# three-phase_inverter.net
KiCad netlist of a schematic drawn in Altium Designer
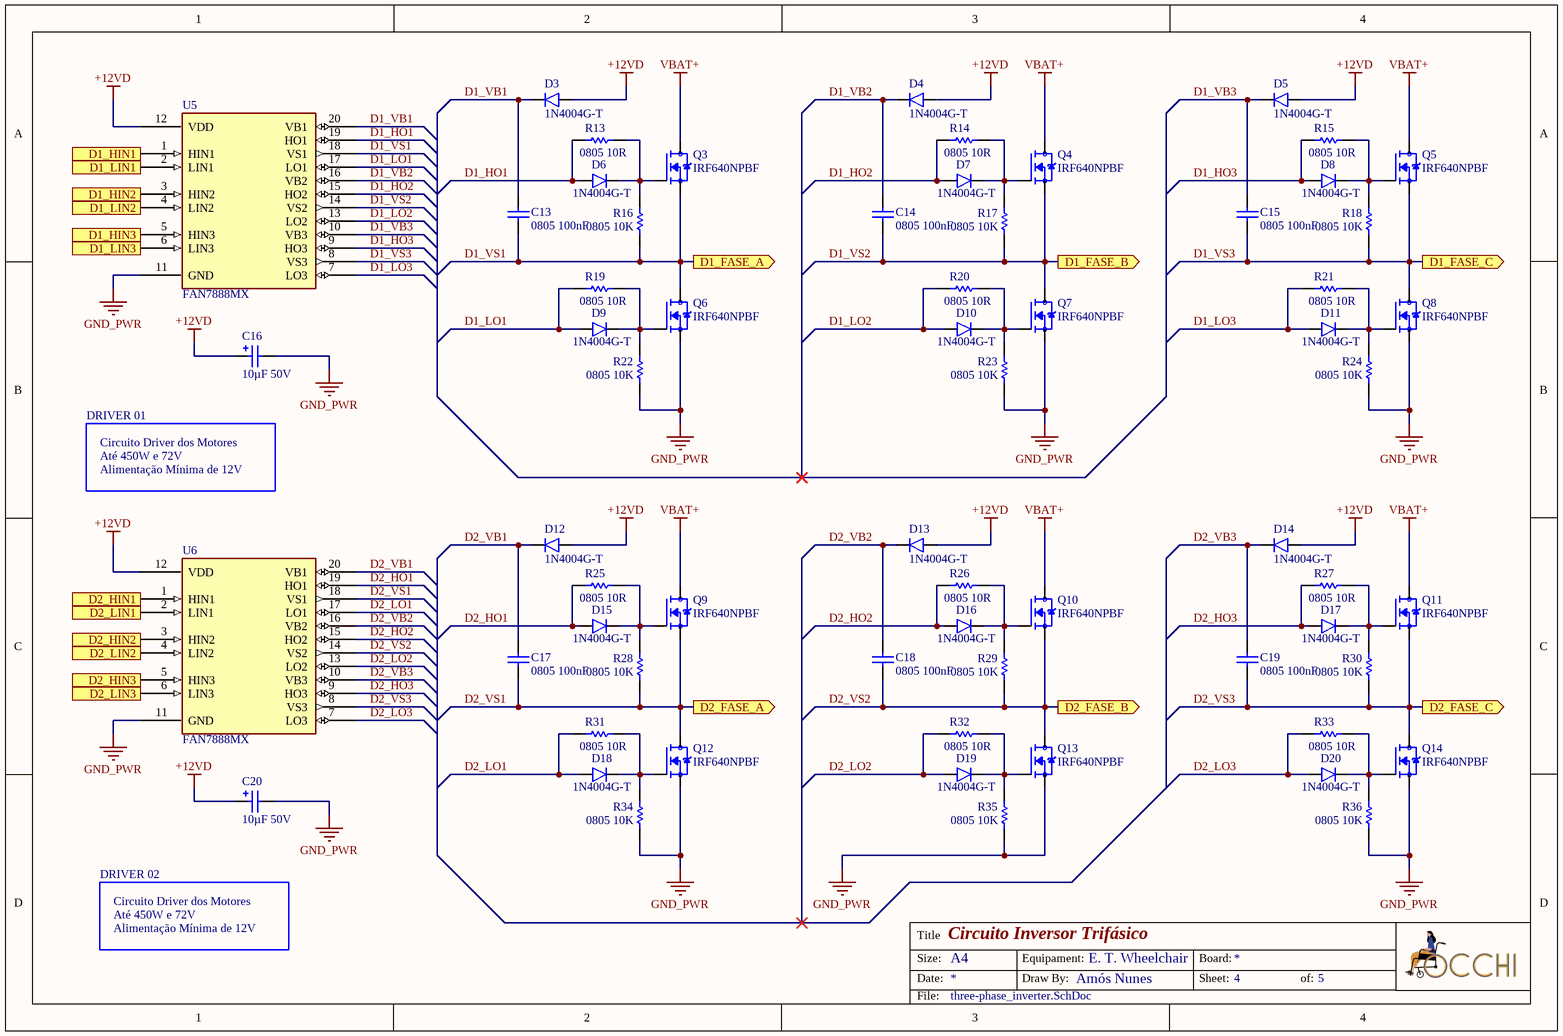
[diagram p0: three-phase_inverter.SchDoc]

(export (version "E")
  (design (tool "Eeschema 10.0.6"))
  (components
    (comp (ref "C13")
      (value "0805 100nF")
      (footprint "CAP0805")
      (description "CC Series 0805 0.1 uF 50 V ±10 % Tolerance X7R SMT Multilayer Ceramic Capacitor")
      (fields
        (field (name "MANUFACTURER") "Yageo")
        (field (name "MANUFACTURER PART NUMBER") "CC0805KRX7R9BB104")
      )
      (libsource (lib "occhi") (part "CC0805KRX7R9BB104"))
    )
    (comp (ref "C14")
      (value "0805 100nF")
      (footprint "CAP0805")
      (description "CC Series 0805 0.1 uF 50 V ±10 % Tolerance X7R SMT Multilayer Ceramic Capacitor")
      (fields
        (field (name "MANUFACTURER") "Yageo")
        (field (name "MANUFACTURER PART NUMBER") "CC0805KRX7R9BB104")
      )
      (libsource (lib "occhi") (part "CC0805KRX7R9BB104"))
    )
    (comp (ref "C15")
      (value "0805 100nF")
      (footprint "CAP0805")
      (description "CC Series 0805 0.1 uF 50 V ±10 % Tolerance X7R SMT Multilayer Ceramic Capacitor")
      (fields
        (field (name "MANUFACTURER") "Yageo")
        (field (name "MANUFACTURER PART NUMBER") "CC0805KRX7R9BB104")
      )
      (libsource (lib "occhi") (part "CC0805KRX7R9BB104"))
    )
    (comp (ref "C16")
      (value "10µF 50V")
      (footprint "CAP_PK/PZ_6P3X11_LOW_RUB")
      (description "10uF ±20% 50V 5000hrs@105°C AEC_D5x11mm_2mm_TM")
      (fields
        (field (name "MANUFACTURER_PART_NUMBER") "16PK330MEFC6.3X11")
        (field (name "MANUFACTURER") "Rubycon")
        (field (name "COPYRIGHT") "Copyright (C) 2021 Ultra Librarian. All rights reserved.")
      )
      (libsource (lib "occhi") (part "50YXF10MEFC5X11"))
    )
    (comp (ref "C17")
      (value "0805 100nF")
      (footprint "CAP0805")
      (description "CC Series 0805 0.1 uF 50 V ±10 % Tolerance X7R SMT Multilayer Ceramic Capacitor")
      (fields
        (field (name "MANUFACTURER") "Yageo")
        (field (name "MANUFACTURER PART NUMBER") "CC0805KRX7R9BB104")
      )
      (libsource (lib "occhi") (part "CC0805KRX7R9BB104"))
    )
    (comp (ref "C18")
      (value "0805 100nF")
      (footprint "CAP0805")
      (description "CC Series 0805 0.1 uF 50 V ±10 % Tolerance X7R SMT Multilayer Ceramic Capacitor")
      (fields
        (field (name "MANUFACTURER") "Yageo")
        (field (name "MANUFACTURER PART NUMBER") "CC0805KRX7R9BB104")
      )
      (libsource (lib "occhi") (part "CC0805KRX7R9BB104"))
    )
    (comp (ref "C19")
      (value "0805 100nF")
      (footprint "CAP0805")
      (description "CC Series 0805 0.1 uF 50 V ±10 % Tolerance X7R SMT Multilayer Ceramic Capacitor")
      (fields
        (field (name "MANUFACTURER") "Yageo")
        (field (name "MANUFACTURER PART NUMBER") "CC0805KRX7R9BB104")
      )
      (libsource (lib "occhi") (part "CC0805KRX7R9BB104"))
    )
    (comp (ref "C20")
      (value "10µF 50V")
      (footprint "CAP_PK/PZ_6P3X11_LOW_RUB")
      (description "10uF ±20% 50V 5000hrs@105°C AEC_D5x11mm_2mm_TM")
      (fields
        (field (name "MANUFACTURER_PART_NUMBER") "16PK330MEFC6.3X11")
        (field (name "MANUFACTURER") "Rubycon")
        (field (name "COPYRIGHT") "Copyright (C) 2021 Ultra Librarian. All rights reserved.")
      )
      (libsource (lib "occhi") (part "50YXF10MEFC5X11"))
    )
    (comp (ref "D3")
      (value "1N4004G-T")
      (footprint "DO41-10")
      (description "Diode Standard Recovery Rectifier 400V 1A 2-Pin DO-41 T/R")
      (fields (field (name "MANUFACTURER") "Diodes"))
      (libsource (lib "occhi") (part "1N4004G-T"))
    )
    (comp (ref "D4")
      (value "1N4004G-T")
      (footprint "DO41-10")
      (description "Diode Standard Recovery Rectifier 400V 1A 2-Pin DO-41 T/R")
      (fields (field (name "MANUFACTURER") "Diodes"))
      (libsource (lib "occhi") (part "1N4004G-T"))
    )
    (comp (ref "D5")
      (value "1N4004G-T")
      (footprint "DO41-10")
      (description "Diode Standard Recovery Rectifier 400V 1A 2-Pin DO-41 T/R")
      (fields (field (name "MANUFACTURER") "Diodes"))
      (libsource (lib "occhi") (part "1N4004G-T"))
    )
    (comp (ref "D6")
      (value "1N4004G-T")
      (footprint "DO41-10")
      (description "Diode Standard Recovery Rectifier 400V 1A 2-Pin DO-41 T/R")
      (fields (field (name "MANUFACTURER") "Diodes"))
      (libsource (lib "occhi") (part "1N4004G-T"))
    )
    (comp (ref "D7")
      (value "1N4004G-T")
      (footprint "DO41-10")
      (description "Diode Standard Recovery Rectifier 400V 1A 2-Pin DO-41 T/R")
      (fields (field (name "MANUFACTURER") "Diodes"))
      (libsource (lib "occhi") (part "1N4004G-T"))
    )
    (comp (ref "D8")
      (value "1N4004G-T")
      (footprint "DO41-10")
      (description "Diode Standard Recovery Rectifier 400V 1A 2-Pin DO-41 T/R")
      (fields (field (name "MANUFACTURER") "Diodes"))
      (libsource (lib "occhi") (part "1N4004G-T"))
    )
    (comp (ref "D9")
      (value "1N4004G-T")
      (footprint "DO41-10")
      (description "Diode Standard Recovery Rectifier 400V 1A 2-Pin DO-41 T/R")
      (fields (field (name "MANUFACTURER") "Diodes"))
      (libsource (lib "occhi") (part "1N4004G-T"))
    )
    (comp (ref "D10")
      (value "1N4004G-T")
      (footprint "DO41-10")
      (description "Diode Standard Recovery Rectifier 400V 1A 2-Pin DO-41 T/R")
      (fields (field (name "MANUFACTURER") "Diodes"))
      (libsource (lib "occhi") (part "1N4004G-T"))
    )
    (comp (ref "D11")
      (value "1N4004G-T")
      (footprint "DO41-10")
      (description "Diode Standard Recovery Rectifier 400V 1A 2-Pin DO-41 T/R")
      (fields (field (name "MANUFACTURER") "Diodes"))
      (libsource (lib "occhi") (part "1N4004G-T"))
    )
    (comp (ref "D12")
      (value "1N4004G-T")
      (footprint "DO41-10")
      (description "Diode Standard Recovery Rectifier 400V 1A 2-Pin DO-41 T/R")
      (fields (field (name "MANUFACTURER") "Diodes"))
      (libsource (lib "occhi") (part "1N4004G-T"))
    )
    (comp (ref "D13")
      (value "1N4004G-T")
      (footprint "DO41-10")
      (description "Diode Standard Recovery Rectifier 400V 1A 2-Pin DO-41 T/R")
      (fields (field (name "MANUFACTURER") "Diodes"))
      (libsource (lib "occhi") (part "1N4004G-T"))
    )
    (comp (ref "D14")
      (value "1N4004G-T")
      (footprint "DO41-10")
      (description "Diode Standard Recovery Rectifier 400V 1A 2-Pin DO-41 T/R")
      (fields (field (name "MANUFACTURER") "Diodes"))
      (libsource (lib "occhi") (part "1N4004G-T"))
    )
    (comp (ref "D15")
      (value "1N4004G-T")
      (footprint "DO41-10")
      (description "Diode Standard Recovery Rectifier 400V 1A 2-Pin DO-41 T/R")
      (fields (field (name "MANUFACTURER") "Diodes"))
      (libsource (lib "occhi") (part "1N4004G-T"))
    )
    (comp (ref "D16")
      (value "1N4004G-T")
      (footprint "DO41-10")
      (description "Diode Standard Recovery Rectifier 400V 1A 2-Pin DO-41 T/R")
      (fields (field (name "MANUFACTURER") "Diodes"))
      (libsource (lib "occhi") (part "1N4004G-T"))
    )
    (comp (ref "D17")
      (value "1N4004G-T")
      (footprint "DO41-10")
      (description "Diode Standard Recovery Rectifier 400V 1A 2-Pin DO-41 T/R")
      (fields (field (name "MANUFACTURER") "Diodes"))
      (libsource (lib "occhi") (part "1N4004G-T"))
    )
    (comp (ref "D18")
      (value "1N4004G-T")
      (footprint "DO41-10")
      (description "Diode Standard Recovery Rectifier 400V 1A 2-Pin DO-41 T/R")
      (fields (field (name "MANUFACTURER") "Diodes"))
      (libsource (lib "occhi") (part "1N4004G-T"))
    )
    (comp (ref "D19")
      (value "1N4004G-T")
      (footprint "DO41-10")
      (description "Diode Standard Recovery Rectifier 400V 1A 2-Pin DO-41 T/R")
      (fields (field (name "MANUFACTURER") "Diodes"))
      (libsource (lib "occhi") (part "1N4004G-T"))
    )
    (comp (ref "D20")
      (value "1N4004G-T")
      (footprint "DO41-10")
      (description "Diode Standard Recovery Rectifier 400V 1A 2-Pin DO-41 T/R")
      (fields (field (name "MANUFACTURER") "Diodes"))
      (libsource (lib "occhi") (part "1N4004G-T"))
    )
    (comp (ref "Q3")
      (value "IRF640NPBF")
      (footprint "TO220AB_VIS")
      (description "Mosfet, Power; N-ch; Vdss 200V; Rds(on) 0.15 Ohm; Id 18A; TO-220AB; Pd 150W; Vgs +/-20V")
      (fields (field (name "MF") "Infineon") (field (name "MANUFACTURER") "International Rectifier"))
      (libsource (lib "occhi") (part "IRF640NPBF"))
    )
    (comp (ref "Q4")
      (value "IRF640NPBF")
      (footprint "TO220AB_VIS")
      (description "Mosfet, Power; N-ch; Vdss 200V; Rds(on) 0.15 Ohm; Id 18A; TO-220AB; Pd 150W; Vgs +/-20V")
      (fields (field (name "MF") "Infineon") (field (name "MANUFACTURER") "International Rectifier"))
      (libsource (lib "occhi") (part "IRF640NPBF"))
    )
    (comp (ref "Q5")
      (value "IRF640NPBF")
      (footprint "TO220AB_VIS")
      (description "Mosfet, Power; N-ch; Vdss 200V; Rds(on) 0.15 Ohm; Id 18A; TO-220AB; Pd 150W; Vgs +/-20V")
      (fields (field (name "MF") "Infineon") (field (name "MANUFACTURER") "International Rectifier"))
      (libsource (lib "occhi") (part "IRF640NPBF"))
    )
    (comp (ref "Q6")
      (value "IRF640NPBF")
      (footprint "TO220AB_VIS")
      (description "Mosfet, Power; N-ch; Vdss 200V; Rds(on) 0.15 Ohm; Id 18A; TO-220AB; Pd 150W; Vgs +/-20V")
      (fields (field (name "MF") "Infineon") (field (name "MANUFACTURER") "International Rectifier"))
      (libsource (lib "occhi") (part "IRF640NPBF"))
    )
    (comp (ref "Q7")
      (value "IRF640NPBF")
      (footprint "TO220AB_VIS")
      (description "Mosfet, Power; N-ch; Vdss 200V; Rds(on) 0.15 Ohm; Id 18A; TO-220AB; Pd 150W; Vgs +/-20V")
      (fields (field (name "MF") "Infineon") (field (name "MANUFACTURER") "International Rectifier"))
      (libsource (lib "occhi") (part "IRF640NPBF"))
    )
    (comp (ref "Q8")
      (value "IRF640NPBF")
      (footprint "TO220AB_VIS")
      (description "Mosfet, Power; N-ch; Vdss 200V; Rds(on) 0.15 Ohm; Id 18A; TO-220AB; Pd 150W; Vgs +/-20V")
      (fields (field (name "MF") "Infineon") (field (name "MANUFACTURER") "International Rectifier"))
      (libsource (lib "occhi") (part "IRF640NPBF"))
    )
    (comp (ref "Q9")
      (value "IRF640NPBF")
      (footprint "TO220AB_VIS")
      (description "Mosfet, Power; N-ch; Vdss 200V; Rds(on) 0.15 Ohm; Id 18A; TO-220AB; Pd 150W; Vgs +/-20V")
      (fields (field (name "MF") "Infineon") (field (name "MANUFACTURER") "International Rectifier"))
      (libsource (lib "occhi") (part "IRF640NPBF"))
    )
    (comp (ref "Q10")
      (value "IRF640NPBF")
      (footprint "TO220AB_VIS")
      (description "Mosfet, Power; N-ch; Vdss 200V; Rds(on) 0.15 Ohm; Id 18A; TO-220AB; Pd 150W; Vgs +/-20V")
      (fields (field (name "MF") "Infineon") (field (name "MANUFACTURER") "International Rectifier"))
      (libsource (lib "occhi") (part "IRF640NPBF"))
    )
    (comp (ref "Q11")
      (value "IRF640NPBF")
      (footprint "TO220AB_VIS")
      (description "Mosfet, Power; N-ch; Vdss 200V; Rds(on) 0.15 Ohm; Id 18A; TO-220AB; Pd 150W; Vgs +/-20V")
      (fields (field (name "MF") "Infineon") (field (name "MANUFACTURER") "International Rectifier"))
      (libsource (lib "occhi") (part "IRF640NPBF"))
    )
    (comp (ref "Q12")
      (value "IRF640NPBF")
      (footprint "TO220AB_VIS")
      (description "Mosfet, Power; N-ch; Vdss 200V; Rds(on) 0.15 Ohm; Id 18A; TO-220AB; Pd 150W; Vgs +/-20V")
      (fields (field (name "MF") "Infineon") (field (name "MANUFACTURER") "International Rectifier"))
      (libsource (lib "occhi") (part "IRF640NPBF"))
    )
    (comp (ref "Q13")
      (value "IRF640NPBF")
      (footprint "TO220AB_VIS")
      (description "Mosfet, Power; N-ch; Vdss 200V; Rds(on) 0.15 Ohm; Id 18A; TO-220AB; Pd 150W; Vgs +/-20V")
      (fields (field (name "MF") "Infineon") (field (name "MANUFACTURER") "International Rectifier"))
      (libsource (lib "occhi") (part "IRF640NPBF"))
    )
    (comp (ref "Q14")
      (value "IRF640NPBF")
      (footprint "TO220AB_VIS")
      (description "Mosfet, Power; N-ch; Vdss 200V; Rds(on) 0.15 Ohm; Id 18A; TO-220AB; Pd 150W; Vgs +/-20V")
      (fields (field (name "MF") "Infineon") (field (name "MANUFACTURER") "International Rectifier"))
      (libsource (lib "occhi") (part "IRF640NPBF"))
    )
    (comp (ref "R13")
      (value "0805 10R")
      (footprint "CAP0805")
      (description "10R Ohms ± 1.00% 0.125W ± 200ppm/℃ 0805")
      (fields
        (field (name "MANUFACTURER") "Yageo")
        (field (name "MANUFACTURER PART NUMBER") "RC0805FR-0710RL")
      )
      (libsource (lib "occhi") (part "RC0805FR-0710RL"))
    )
    (comp (ref "R14")
      (value "0805 10R")
      (footprint "CAP0805")
      (description "10R Ohms ± 1.00% 0.125W ± 200ppm/℃ 0805")
      (fields
        (field (name "MANUFACTURER") "Yageo")
        (field (name "MANUFACTURER PART NUMBER") "RC0805FR-0710RL")
      )
      (libsource (lib "occhi") (part "RC0805FR-0710RL"))
    )
    (comp (ref "R15")
      (value "0805 10R")
      (footprint "CAP0805")
      (description "10R Ohms ± 1.00% 0.125W ± 200ppm/℃ 0805")
      (fields
        (field (name "MANUFACTURER") "Yageo")
        (field (name "MANUFACTURER PART NUMBER") "RC0805FR-0710RL")
      )
      (libsource (lib "occhi") (part "RC0805FR-0710RL"))
    )
    (comp (ref "R16")
      (value "0805 10K")
      (footprint "RES0805")
      (description "10K Omhs 0805 ± 1.00% 0.125W ± 100ppm/℃")
      (fields
        (field (name "MANUFACTURER") "Yageo")
        (field (name "MANUFACTURER PART NUMBER") "RC0603FR-0710KL")
      )
      (libsource (lib "occhi") (part "RC0805FR-0710KL"))
    )
    (comp (ref "R17")
      (value "0805 10K")
      (footprint "RES0805")
      (description "10K Omhs 0805 ± 1.00% 0.125W ± 100ppm/℃")
      (fields
        (field (name "MANUFACTURER") "Yageo")
        (field (name "MANUFACTURER PART NUMBER") "RC0603FR-0710KL")
      )
      (libsource (lib "occhi") (part "RC0805FR-0710KL"))
    )
    (comp (ref "R18")
      (value "0805 10K")
      (footprint "RES0805")
      (description "10K Omhs 0805 ± 1.00% 0.125W ± 100ppm/℃")
      (fields
        (field (name "MANUFACTURER") "Yageo")
        (field (name "MANUFACTURER PART NUMBER") "RC0603FR-0710KL")
      )
      (libsource (lib "occhi") (part "RC0805FR-0710KL"))
    )
    (comp (ref "R19")
      (value "0805 10R")
      (footprint "CAP0805")
      (description "10R Ohms ± 1.00% 0.125W ± 200ppm/℃ 0805")
      (fields
        (field (name "MANUFACTURER") "Yageo")
        (field (name "MANUFACTURER PART NUMBER") "RC0805FR-0710RL")
      )
      (libsource (lib "occhi") (part "RC0805FR-0710RL"))
    )
    (comp (ref "R20")
      (value "0805 10R")
      (footprint "CAP0805")
      (description "10R Ohms ± 1.00% 0.125W ± 200ppm/℃ 0805")
      (fields
        (field (name "MANUFACTURER") "Yageo")
        (field (name "MANUFACTURER PART NUMBER") "RC0805FR-0710RL")
      )
      (libsource (lib "occhi") (part "RC0805FR-0710RL"))
    )
    (comp (ref "R21")
      (value "0805 10R")
      (footprint "CAP0805")
      (description "10R Ohms ± 1.00% 0.125W ± 200ppm/℃ 0805")
      (fields
        (field (name "MANUFACTURER") "Yageo")
        (field (name "MANUFACTURER PART NUMBER") "RC0805FR-0710RL")
      )
      (libsource (lib "occhi") (part "RC0805FR-0710RL"))
    )
    (comp (ref "R22")
      (value "0805 10K")
      (footprint "RES0805")
      (description "10K Omhs 0805 ± 1.00% 0.125W ± 100ppm/℃")
      (fields
        (field (name "MANUFACTURER") "Yageo")
        (field (name "MANUFACTURER PART NUMBER") "RC0603FR-0710KL")
      )
      (libsource (lib "occhi") (part "RC0805FR-0710KL"))
    )
    (comp (ref "R23")
      (value "0805 10K")
      (footprint "RES0805")
      (description "10K Omhs 0805 ± 1.00% 0.125W ± 100ppm/℃")
      (fields
        (field (name "MANUFACTURER") "Yageo")
        (field (name "MANUFACTURER PART NUMBER") "RC0603FR-0710KL")
      )
      (libsource (lib "occhi") (part "RC0805FR-0710KL"))
    )
    (comp (ref "R24")
      (value "0805 10K")
      (footprint "RES0805")
      (description "10K Omhs 0805 ± 1.00% 0.125W ± 100ppm/℃")
      (fields
        (field (name "MANUFACTURER") "Yageo")
        (field (name "MANUFACTURER PART NUMBER") "RC0603FR-0710KL")
      )
      (libsource (lib "occhi") (part "RC0805FR-0710KL"))
    )
    (comp (ref "R25")
      (value "0805 10R")
      (footprint "CAP0805")
      (description "10R Ohms ± 1.00% 0.125W ± 200ppm/℃ 0805")
      (fields
        (field (name "MANUFACTURER") "Yageo")
        (field (name "MANUFACTURER PART NUMBER") "RC0805FR-0710RL")
      )
      (libsource (lib "occhi") (part "RC0805FR-0710RL"))
    )
    (comp (ref "R26")
      (value "0805 10R")
      (footprint "CAP0805")
      (description "10R Ohms ± 1.00% 0.125W ± 200ppm/℃ 0805")
      (fields
        (field (name "MANUFACTURER") "Yageo")
        (field (name "MANUFACTURER PART NUMBER") "RC0805FR-0710RL")
      )
      (libsource (lib "occhi") (part "RC0805FR-0710RL"))
    )
    (comp (ref "R27")
      (value "0805 10R")
      (footprint "CAP0805")
      (description "10R Ohms ± 1.00% 0.125W ± 200ppm/℃ 0805")
      (fields
        (field (name "MANUFACTURER") "Yageo")
        (field (name "MANUFACTURER PART NUMBER") "RC0805FR-0710RL")
      )
      (libsource (lib "occhi") (part "RC0805FR-0710RL"))
    )
    (comp (ref "R28")
      (value "0805 10K")
      (footprint "RES0805")
      (description "10K Omhs 0805 ± 1.00% 0.125W ± 100ppm/℃")
      (fields
        (field (name "MANUFACTURER") "Yageo")
        (field (name "MANUFACTURER PART NUMBER") "RC0603FR-0710KL")
      )
      (libsource (lib "occhi") (part "RC0805FR-0710KL"))
    )
    (comp (ref "R29")
      (value "0805 10K")
      (footprint "RES0805")
      (description "10K Omhs 0805 ± 1.00% 0.125W ± 100ppm/℃")
      (fields
        (field (name "MANUFACTURER") "Yageo")
        (field (name "MANUFACTURER PART NUMBER") "RC0603FR-0710KL")
      )
      (libsource (lib "occhi") (part "RC0805FR-0710KL"))
    )
    (comp (ref "R30")
      (value "0805 10K")
      (footprint "RES0805")
      (description "10K Omhs 0805 ± 1.00% 0.125W ± 100ppm/℃")
      (fields
        (field (name "MANUFACTURER") "Yageo")
        (field (name "MANUFACTURER PART NUMBER") "RC0603FR-0710KL")
      )
      (libsource (lib "occhi") (part "RC0805FR-0710KL"))
    )
    (comp (ref "R31")
      (value "0805 10R")
      (footprint "CAP0805")
      (description "10R Ohms ± 1.00% 0.125W ± 200ppm/℃ 0805")
      (fields
        (field (name "MANUFACTURER") "Yageo")
        (field (name "MANUFACTURER PART NUMBER") "RC0805FR-0710RL")
      )
      (libsource (lib "occhi") (part "RC0805FR-0710RL"))
    )
    (comp (ref "R32")
      (value "0805 10R")
      (footprint "CAP0805")
      (description "10R Ohms ± 1.00% 0.125W ± 200ppm/℃ 0805")
      (fields
        (field (name "MANUFACTURER") "Yageo")
        (field (name "MANUFACTURER PART NUMBER") "RC0805FR-0710RL")
      )
      (libsource (lib "occhi") (part "RC0805FR-0710RL"))
    )
    (comp (ref "R33")
      (value "0805 10R")
      (footprint "CAP0805")
      (description "10R Ohms ± 1.00% 0.125W ± 200ppm/℃ 0805")
      (fields
        (field (name "MANUFACTURER") "Yageo")
        (field (name "MANUFACTURER PART NUMBER") "RC0805FR-0710RL")
      )
      (libsource (lib "occhi") (part "RC0805FR-0710RL"))
    )
    (comp (ref "R34")
      (value "0805 10K")
      (footprint "RES0805")
      (description "10K Omhs 0805 ± 1.00% 0.125W ± 100ppm/℃")
      (fields
        (field (name "MANUFACTURER") "Yageo")
        (field (name "MANUFACTURER PART NUMBER") "RC0603FR-0710KL")
      )
      (libsource (lib "occhi") (part "RC0805FR-0710KL"))
    )
    (comp (ref "R35")
      (value "0805 10K")
      (footprint "RES0805")
      (description "10K Omhs 0805 ± 1.00% 0.125W ± 100ppm/℃")
      (fields
        (field (name "MANUFACTURER") "Yageo")
        (field (name "MANUFACTURER PART NUMBER") "RC0603FR-0710KL")
      )
      (libsource (lib "occhi") (part "RC0805FR-0710KL"))
    )
    (comp (ref "R36")
      (value "0805 10K")
      (footprint "RES0805")
      (description "10K Omhs 0805 ± 1.00% 0.125W ± 100ppm/℃")
      (fields
        (field (name "MANUFACTURER") "Yageo")
        (field (name "MANUFACTURER PART NUMBER") "RC0603FR-0710KL")
      )
      (libsource (lib "occhi") (part "RC0805FR-0710KL"))
    )
    (comp (ref "U5")
      (value "FAN7888MX")
      (footprint "SOIC20_13X7P6_ONS")
      (description "Driver 200V 0.65A 6-OUT Hi/Lo Side Half Brdg Non-Inv 20-Pin SOIC W T/R")
      (fields
        (field (name "MANUFACTURER") "ON Semiconductor / Fairchild")
        (field (name "COPYRIGHT") "Copyright (C) 2022 Ultra Librarian. All rights reserved.")
      )
      (libsource (lib "occhi") (part "FAN7888MX"))
    )
    (comp (ref "U6")
      (value "FAN7888MX")
      (footprint "SOIC20_13X7P6_ONS")
      (description "Driver 200V 0.65A 6-OUT Hi/Lo Side Half Brdg Non-Inv 20-Pin SOIC W T/R")
      (fields
        (field (name "MANUFACTURER") "ON Semiconductor / Fairchild")
        (field (name "COPYRIGHT") "Copyright (C) 2022 Ultra Librarian. All rights reserved.")
      )
      (libsource (lib "occhi") (part "FAN7888MX"))
    )
  )
  (nets
    (net (code "1") (name "+12VD") (class "Default")
      (node (ref "C16") (pin "1") (pinfunction "1_1") (pintype "passive"))
      (node (ref "C20") (pin "1") (pinfunction "1_1") (pintype "passive"))
      (node (ref "D12") (pin "2") (pinfunction "A_2") (pintype "passive"))
      (node (ref "D13") (pin "2") (pinfunction "A_2") (pintype "passive"))
      (node (ref "D14") (pin "2") (pinfunction "A_2") (pintype "passive"))
      (node (ref "D3") (pin "2") (pinfunction "A_2") (pintype "passive"))
      (node (ref "D4") (pin "2") (pinfunction "A_2") (pintype "passive"))
      (node (ref "D5") (pin "2") (pinfunction "A_2") (pintype "passive"))
      (node (ref "U5") (pin "12") (pinfunction "VDD_12") (pintype "power_in"))
      (node (ref "U6") (pin "12") (pinfunction "VDD_12") (pintype "power_in"))
    )
    (net (code "2") (name "/D1_HIN1") (class "Default")
      (node (ref "U5") (pin "1") (pinfunction "HIN1_1") (pintype "input"))
    )
    (net (code "3") (name "/D1_HIN2") (class "Default")
      (node (ref "U5") (pin "3") (pinfunction "HIN2_3") (pintype "input"))
    )
    (net (code "4") (name "/D1_HIN3") (class "Default")
      (node (ref "U5") (pin "5") (pinfunction "HIN3_5") (pintype "input"))
    )
    (net (code "5") (name "/D1_HO1") (class "Default")
      (node (ref "D6") (pin "2") (pinfunction "A_2") (pintype "passive"))
      (node (ref "R13") (pin "1") (pinfunction "1_1") (pintype "passive"))
      (node (ref "U5") (pin "19") (pinfunction "HO1_19") (pintype "bidirectional"))
    )
    (net (code "6") (name "/D1_HO2") (class "Default")
      (node (ref "D7") (pin "2") (pinfunction "A_2") (pintype "passive"))
      (node (ref "R14") (pin "1") (pinfunction "1_1") (pintype "passive"))
      (node (ref "U5") (pin "15") (pinfunction "HO2_15") (pintype "bidirectional"))
    )
    (net (code "7") (name "/D1_HO3") (class "Default")
      (node (ref "D8") (pin "2") (pinfunction "A_2") (pintype "passive"))
      (node (ref "R15") (pin "1") (pinfunction "1_1") (pintype "passive"))
      (node (ref "U5") (pin "9") (pinfunction "HO3_9") (pintype "bidirectional"))
    )
    (net (code "8") (name "/D1_LIN1") (class "Default")
      (node (ref "U5") (pin "2") (pinfunction "LIN1_2") (pintype "input"))
    )
    (net (code "9") (name "/D1_LIN2") (class "Default")
      (node (ref "U5") (pin "4") (pinfunction "LIN2_4") (pintype "input"))
    )
    (net (code "10") (name "/D1_LIN3") (class "Default")
      (node (ref "U5") (pin "6") (pinfunction "LIN3_6") (pintype "input"))
    )
    (net (code "11") (name "/D1_LO1") (class "Default")
      (node (ref "D9") (pin "2") (pinfunction "A_2") (pintype "passive"))
      (node (ref "R19") (pin "1") (pinfunction "1_1") (pintype "passive"))
      (node (ref "U5") (pin "17") (pinfunction "LO1_17") (pintype "bidirectional"))
    )
    (net (code "12") (name "/D1_LO2") (class "Default")
      (node (ref "D10") (pin "2") (pinfunction "A_2") (pintype "passive"))
      (node (ref "R20") (pin "1") (pinfunction "1_1") (pintype "passive"))
      (node (ref "U5") (pin "13") (pinfunction "LO2_13") (pintype "bidirectional"))
    )
    (net (code "13") (name "/D1_LO3") (class "Default")
      (node (ref "D11") (pin "2") (pinfunction "A_2") (pintype "passive"))
      (node (ref "R21") (pin "1") (pinfunction "1_1") (pintype "passive"))
      (node (ref "U5") (pin "7") (pinfunction "LO3_7") (pintype "bidirectional"))
    )
    (net (code "14") (name "/D1_VB1") (class "Default")
      (node (ref "C13") (pin "1") (pinfunction "1_1") (pintype "passive"))
      (node (ref "D3") (pin "1") (pinfunction "K_1") (pintype "passive"))
      (node (ref "U5") (pin "20") (pinfunction "VB1_20") (pintype "bidirectional"))
    )
    (net (code "15") (name "/D1_VB2") (class "Default")
      (node (ref "C14") (pin "1") (pinfunction "1_1") (pintype "passive"))
      (node (ref "D4") (pin "1") (pinfunction "K_1") (pintype "passive"))
      (node (ref "U5") (pin "16") (pinfunction "VB2_16") (pintype "bidirectional"))
    )
    (net (code "16") (name "/D1_VB3") (class "Default")
      (node (ref "C15") (pin "1") (pinfunction "1_1") (pintype "passive"))
      (node (ref "D5") (pin "1") (pinfunction "K_1") (pintype "passive"))
      (node (ref "U5") (pin "10") (pinfunction "VB3_10") (pintype "bidirectional"))
    )
    (net (code "17") (name "/D1_VS1") (class "Default")
      (node (ref "C13") (pin "2") (pinfunction "2_2") (pintype "passive"))
      (node (ref "Q3") (pin "3") (pinfunction "S_3") (pintype "passive"))
      (node (ref "Q6") (pin "2") (pinfunction "D_2") (pintype "passive"))
      (node (ref "R16") (pin "2") (pinfunction "2_2") (pintype "passive"))
      (node (ref "U5") (pin "18") (pinfunction "VS1_18") (pintype "output"))
    )
    (net (code "18") (name "/D1_VS2") (class "Default")
      (node (ref "C14") (pin "2") (pinfunction "2_2") (pintype "passive"))
      (node (ref "Q4") (pin "3") (pinfunction "S_3") (pintype "passive"))
      (node (ref "Q7") (pin "2") (pinfunction "D_2") (pintype "passive"))
      (node (ref "R17") (pin "2") (pinfunction "2_2") (pintype "passive"))
      (node (ref "U5") (pin "14") (pinfunction "VS2_14") (pintype "output"))
    )
    (net (code "19") (name "/D1_VS3") (class "Default")
      (node (ref "C15") (pin "2") (pinfunction "2_2") (pintype "passive"))
      (node (ref "Q5") (pin "3") (pinfunction "S_3") (pintype "passive"))
      (node (ref "Q8") (pin "2") (pinfunction "D_2") (pintype "passive"))
      (node (ref "R18") (pin "2") (pinfunction "2_2") (pintype "passive"))
      (node (ref "U5") (pin "8") (pinfunction "VS3_8") (pintype "output"))
    )
    (net (code "20") (name "/D2_HIN1") (class "Default")
      (node (ref "U6") (pin "1") (pinfunction "HIN1_1") (pintype "input"))
    )
    (net (code "21") (name "/D2_HIN2") (class "Default")
      (node (ref "U6") (pin "3") (pinfunction "HIN2_3") (pintype "input"))
    )
    (net (code "22") (name "/D2_HIN3") (class "Default")
      (node (ref "U6") (pin "5") (pinfunction "HIN3_5") (pintype "input"))
    )
    (net (code "23") (name "/D2_HO1") (class "Default")
      (node (ref "D15") (pin "2") (pinfunction "A_2") (pintype "passive"))
      (node (ref "R25") (pin "1") (pinfunction "1_1") (pintype "passive"))
      (node (ref "U6") (pin "19") (pinfunction "HO1_19") (pintype "bidirectional"))
    )
    (net (code "24") (name "/D2_HO2") (class "Default")
      (node (ref "D16") (pin "2") (pinfunction "A_2") (pintype "passive"))
      (node (ref "R26") (pin "1") (pinfunction "1_1") (pintype "passive"))
      (node (ref "U6") (pin "15") (pinfunction "HO2_15") (pintype "bidirectional"))
    )
    (net (code "25") (name "/D2_HO3") (class "Default")
      (node (ref "D17") (pin "2") (pinfunction "A_2") (pintype "passive"))
      (node (ref "R27") (pin "1") (pinfunction "1_1") (pintype "passive"))
      (node (ref "U6") (pin "9") (pinfunction "HO3_9") (pintype "bidirectional"))
    )
    (net (code "26") (name "/D2_LIN1") (class "Default")
      (node (ref "U6") (pin "2") (pinfunction "LIN1_2") (pintype "input"))
    )
    (net (code "27") (name "/D2_LIN2") (class "Default")
      (node (ref "U6") (pin "4") (pinfunction "LIN2_4") (pintype "input"))
    )
    (net (code "28") (name "/D2_LIN3") (class "Default")
      (node (ref "U6") (pin "6") (pinfunction "LIN3_6") (pintype "input"))
    )
    (net (code "29") (name "/D2_LO1") (class "Default")
      (node (ref "D18") (pin "2") (pinfunction "A_2") (pintype "passive"))
      (node (ref "R31") (pin "1") (pinfunction "1_1") (pintype "passive"))
      (node (ref "U6") (pin "17") (pinfunction "LO1_17") (pintype "bidirectional"))
    )
    (net (code "30") (name "/D2_LO2") (class "Default")
      (node (ref "D19") (pin "2") (pinfunction "A_2") (pintype "passive"))
      (node (ref "R32") (pin "1") (pinfunction "1_1") (pintype "passive"))
      (node (ref "U6") (pin "13") (pinfunction "LO2_13") (pintype "bidirectional"))
    )
    (net (code "31") (name "/D2_LO3") (class "Default")
      (node (ref "D20") (pin "2") (pinfunction "A_2") (pintype "passive"))
      (node (ref "R33") (pin "1") (pinfunction "1_1") (pintype "passive"))
      (node (ref "U6") (pin "7") (pinfunction "LO3_7") (pintype "bidirectional"))
    )
    (net (code "32") (name "/D2_VB1") (class "Default")
      (node (ref "C17") (pin "1") (pinfunction "1_1") (pintype "passive"))
      (node (ref "D12") (pin "1") (pinfunction "K_1") (pintype "passive"))
      (node (ref "U6") (pin "20") (pinfunction "VB1_20") (pintype "bidirectional"))
    )
    (net (code "33") (name "/D2_VB2") (class "Default")
      (node (ref "C18") (pin "1") (pinfunction "1_1") (pintype "passive"))
      (node (ref "D13") (pin "1") (pinfunction "K_1") (pintype "passive"))
      (node (ref "U6") (pin "16") (pinfunction "VB2_16") (pintype "bidirectional"))
    )
    (net (code "34") (name "/D2_VB3") (class "Default")
      (node (ref "C19") (pin "1") (pinfunction "1_1") (pintype "passive"))
      (node (ref "D14") (pin "1") (pinfunction "K_1") (pintype "passive"))
      (node (ref "U6") (pin "10") (pinfunction "VB3_10") (pintype "bidirectional"))
    )
    (net (code "35") (name "/D2_VS1") (class "Default")
      (node (ref "C17") (pin "2") (pinfunction "2_2") (pintype "passive"))
      (node (ref "Q12") (pin "2") (pinfunction "D_2") (pintype "passive"))
      (node (ref "Q9") (pin "3") (pinfunction "S_3") (pintype "passive"))
      (node (ref "R28") (pin "2") (pinfunction "2_2") (pintype "passive"))
      (node (ref "U6") (pin "18") (pinfunction "VS1_18") (pintype "output"))
    )
    (net (code "36") (name "/D2_VS2") (class "Default")
      (node (ref "C18") (pin "2") (pinfunction "2_2") (pintype "passive"))
      (node (ref "Q10") (pin "3") (pinfunction "S_3") (pintype "passive"))
      (node (ref "Q13") (pin "2") (pinfunction "D_2") (pintype "passive"))
      (node (ref "R29") (pin "2") (pinfunction "2_2") (pintype "passive"))
      (node (ref "U6") (pin "14") (pinfunction "VS2_14") (pintype "output"))
    )
    (net (code "37") (name "/D2_VS3") (class "Default")
      (node (ref "C19") (pin "2") (pinfunction "2_2") (pintype "passive"))
      (node (ref "Q11") (pin "3") (pinfunction "S_3") (pintype "passive"))
      (node (ref "Q14") (pin "2") (pinfunction "D_2") (pintype "passive"))
      (node (ref "R30") (pin "2") (pinfunction "2_2") (pintype "passive"))
      (node (ref "U6") (pin "8") (pinfunction "VS3_8") (pintype "output"))
    )
    (net (code "38") (name "GND_PWR") (class "Default")
      (node (ref "C16") (pin "2") (pinfunction "2_2") (pintype "passive"))
      (node (ref "C20") (pin "2") (pinfunction "2_2") (pintype "passive"))
      (node (ref "Q12") (pin "3") (pinfunction "S_3") (pintype "passive"))
      (node (ref "Q13") (pin "3") (pinfunction "S_3") (pintype "passive"))
      (node (ref "Q14") (pin "3") (pinfunction "S_3") (pintype "passive"))
      (node (ref "Q6") (pin "3") (pinfunction "S_3") (pintype "passive"))
      (node (ref "Q7") (pin "3") (pinfunction "S_3") (pintype "passive"))
      (node (ref "Q8") (pin "3") (pinfunction "S_3") (pintype "passive"))
      (node (ref "R22") (pin "2") (pinfunction "2_2") (pintype "passive"))
      (node (ref "R23") (pin "2") (pinfunction "2_2") (pintype "passive"))
      (node (ref "R24") (pin "2") (pinfunction "2_2") (pintype "passive"))
      (node (ref "R34") (pin "2") (pinfunction "2_2") (pintype "passive"))
      (node (ref "R35") (pin "2") (pinfunction "2_2") (pintype "passive"))
      (node (ref "R36") (pin "2") (pinfunction "2_2") (pintype "passive"))
      (node (ref "U5") (pin "11") (pinfunction "GND_11") (pintype "passive"))
      (node (ref "U6") (pin "11") (pinfunction "GND_11") (pintype "passive"))
    )
    (net (code "39") (name "Net-(D6-K)") (class "Default")
      (node (ref "D6") (pin "1") (pinfunction "K_1") (pintype "passive"))
      (node (ref "Q3") (pin "1") (pinfunction "G_1") (pintype "passive"))
      (node (ref "R13") (pin "2") (pinfunction "2_2") (pintype "passive"))
      (node (ref "R16") (pin "1") (pinfunction "1_1") (pintype "passive"))
    )
    (net (code "40") (name "Net-(D7-K)") (class "Default")
      (node (ref "D7") (pin "1") (pinfunction "K_1") (pintype "passive"))
      (node (ref "Q4") (pin "1") (pinfunction "G_1") (pintype "passive"))
      (node (ref "R14") (pin "2") (pinfunction "2_2") (pintype "passive"))
      (node (ref "R17") (pin "1") (pinfunction "1_1") (pintype "passive"))
    )
    (net (code "41") (name "Net-(D8-K)") (class "Default")
      (node (ref "D8") (pin "1") (pinfunction "K_1") (pintype "passive"))
      (node (ref "Q5") (pin "1") (pinfunction "G_1") (pintype "passive"))
      (node (ref "R15") (pin "2") (pinfunction "2_2") (pintype "passive"))
      (node (ref "R18") (pin "1") (pinfunction "1_1") (pintype "passive"))
    )
    (net (code "42") (name "Net-(D9-K)") (class "Default")
      (node (ref "D9") (pin "1") (pinfunction "K_1") (pintype "passive"))
      (node (ref "Q6") (pin "1") (pinfunction "G_1") (pintype "passive"))
      (node (ref "R19") (pin "2") (pinfunction "2_2") (pintype "passive"))
      (node (ref "R22") (pin "1") (pinfunction "1_1") (pintype "passive"))
    )
    (net (code "43") (name "Net-(D10-K)") (class "Default")
      (node (ref "D10") (pin "1") (pinfunction "K_1") (pintype "passive"))
      (node (ref "Q7") (pin "1") (pinfunction "G_1") (pintype "passive"))
      (node (ref "R20") (pin "2") (pinfunction "2_2") (pintype "passive"))
      (node (ref "R23") (pin "1") (pinfunction "1_1") (pintype "passive"))
    )
    (net (code "44") (name "Net-(D11-K)") (class "Default")
      (node (ref "D11") (pin "1") (pinfunction "K_1") (pintype "passive"))
      (node (ref "Q8") (pin "1") (pinfunction "G_1") (pintype "passive"))
      (node (ref "R21") (pin "2") (pinfunction "2_2") (pintype "passive"))
      (node (ref "R24") (pin "1") (pinfunction "1_1") (pintype "passive"))
    )
    (net (code "45") (name "Net-(D15-K)") (class "Default")
      (node (ref "D15") (pin "1") (pinfunction "K_1") (pintype "passive"))
      (node (ref "Q9") (pin "1") (pinfunction "G_1") (pintype "passive"))
      (node (ref "R25") (pin "2") (pinfunction "2_2") (pintype "passive"))
      (node (ref "R28") (pin "1") (pinfunction "1_1") (pintype "passive"))
    )
    (net (code "46") (name "Net-(D16-K)") (class "Default")
      (node (ref "D16") (pin "1") (pinfunction "K_1") (pintype "passive"))
      (node (ref "Q10") (pin "1") (pinfunction "G_1") (pintype "passive"))
      (node (ref "R26") (pin "2") (pinfunction "2_2") (pintype "passive"))
      (node (ref "R29") (pin "1") (pinfunction "1_1") (pintype "passive"))
    )
    (net (code "47") (name "Net-(D17-K)") (class "Default")
      (node (ref "D17") (pin "1") (pinfunction "K_1") (pintype "passive"))
      (node (ref "Q11") (pin "1") (pinfunction "G_1") (pintype "passive"))
      (node (ref "R27") (pin "2") (pinfunction "2_2") (pintype "passive"))
      (node (ref "R30") (pin "1") (pinfunction "1_1") (pintype "passive"))
    )
    (net (code "48") (name "Net-(D18-K)") (class "Default")
      (node (ref "D18") (pin "1") (pinfunction "K_1") (pintype "passive"))
      (node (ref "Q12") (pin "1") (pinfunction "G_1") (pintype "passive"))
      (node (ref "R31") (pin "2") (pinfunction "2_2") (pintype "passive"))
      (node (ref "R34") (pin "1") (pinfunction "1_1") (pintype "passive"))
    )
    (net (code "49") (name "Net-(D19-K)") (class "Default")
      (node (ref "D19") (pin "1") (pinfunction "K_1") (pintype "passive"))
      (node (ref "Q13") (pin "1") (pinfunction "G_1") (pintype "passive"))
      (node (ref "R32") (pin "2") (pinfunction "2_2") (pintype "passive"))
      (node (ref "R35") (pin "1") (pinfunction "1_1") (pintype "passive"))
    )
    (net (code "50") (name "Net-(D20-K)") (class "Default")
      (node (ref "D20") (pin "1") (pinfunction "K_1") (pintype "passive"))
      (node (ref "Q14") (pin "1") (pinfunction "G_1") (pintype "passive"))
      (node (ref "R33") (pin "2") (pinfunction "2_2") (pintype "passive"))
      (node (ref "R36") (pin "1") (pinfunction "1_1") (pintype "passive"))
    )
    (net (code "51") (name "VBAT+") (class "Default")
      (node (ref "Q10") (pin "2") (pinfunction "D_2") (pintype "passive"))
      (node (ref "Q11") (pin "2") (pinfunction "D_2") (pintype "passive"))
      (node (ref "Q3") (pin "2") (pinfunction "D_2") (pintype "passive"))
      (node (ref "Q4") (pin "2") (pinfunction "D_2") (pintype "passive"))
      (node (ref "Q5") (pin "2") (pinfunction "D_2") (pintype "passive"))
      (node (ref "Q9") (pin "2") (pinfunction "D_2") (pintype "passive"))
    )
  )
)
